# Sunboost.net
KiCad netlist of a schematic drawn in Altium Designer
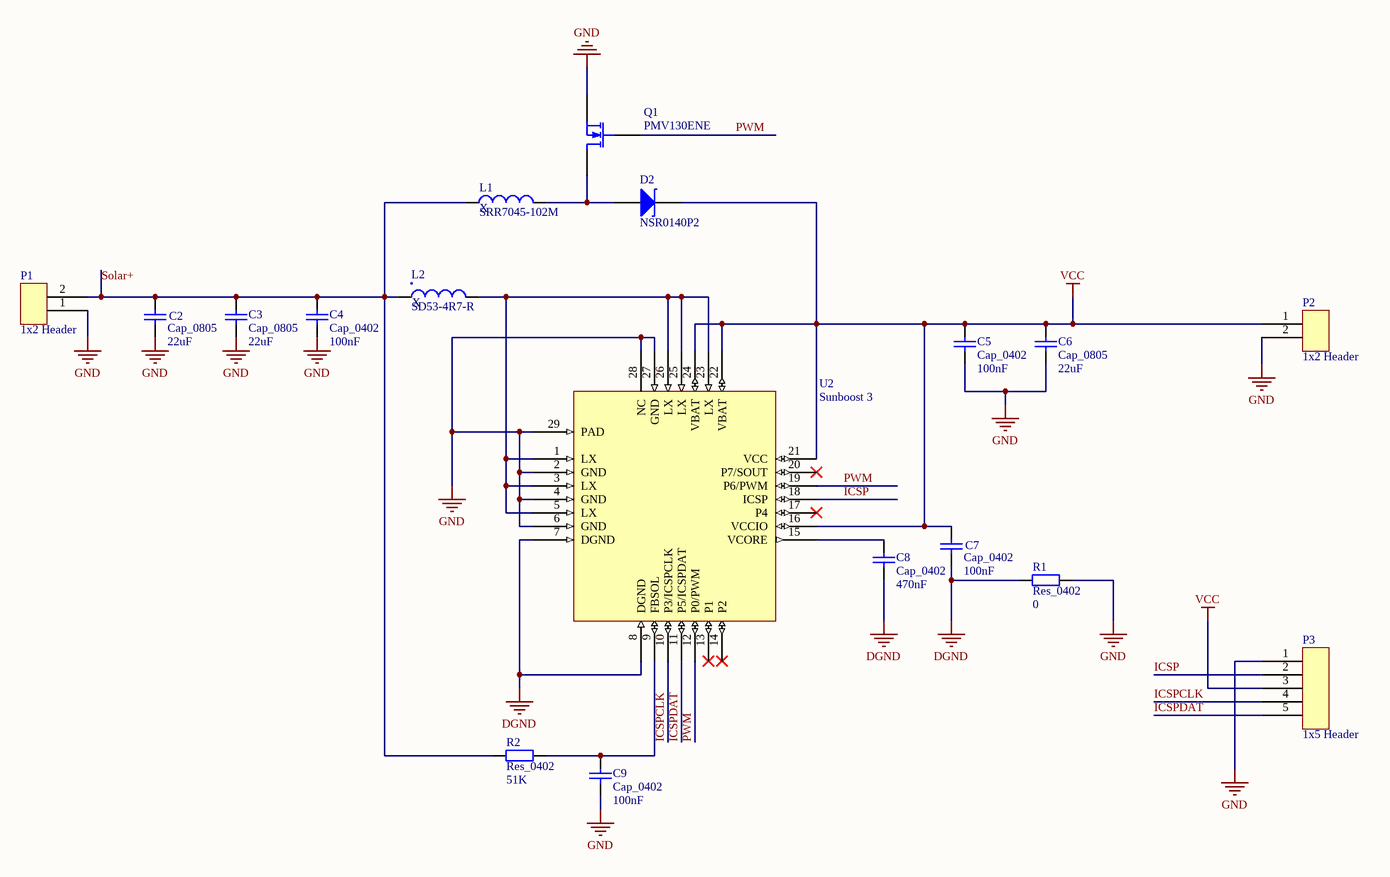
[diagram p0: Sunboost.SchDoc]

(export (version "E")
  (design (tool "Eeschema 10.0.6"))
  (components
    (comp (ref "C2")
      (value "Cap_0805")
      (footprint "0805")
      (description "Capacitor")
      (fields (field (name "ALTIUM_VALUE") "22uF") (field (name "PUBLISHER") "Altium Limited"))
      (libsource (lib "Schematic_Components") (part "Cap_0805"))
    )
    (comp (ref "C3")
      (value "Cap_0805")
      (footprint "0805")
      (description "Capacitor")
      (fields (field (name "ALTIUM_VALUE") "22uF") (field (name "PUBLISHER") "Altium Limited"))
      (libsource (lib "Schematic_Components") (part "Cap_0805"))
    )
    (comp (ref "C4")
      (value "Cap_0402")
      (footprint "0402")
      (description "Capacitor")
      (fields (field (name "ALTIUM_VALUE") "100nF") (field (name "PUBLISHER") "Altium Limited"))
      (libsource (lib "Schematic_Components") (part "Cap_0402"))
    )
    (comp (ref "C5")
      (value "Cap_0402")
      (footprint "0402")
      (description "Capacitor")
      (fields (field (name "ALTIUM_VALUE") "100nF") (field (name "PUBLISHER") "Altium Limited"))
      (libsource (lib "Schematic_Components") (part "Cap_0402"))
    )
    (comp (ref "C6")
      (value "Cap_0805")
      (footprint "0805")
      (description "Capacitor")
      (fields (field (name "ALTIUM_VALUE") "22uF") (field (name "PUBLISHER") "Altium Limited"))
      (libsource (lib "Schematic_Components") (part "Cap_0805"))
    )
    (comp (ref "C7")
      (value "Cap_0402")
      (footprint "0402")
      (description "Capacitor")
      (fields (field (name "ALTIUM_VALUE") "100nF") (field (name "PUBLISHER") "Altium Limited"))
      (libsource (lib "Schematic_Components") (part "Cap_0402"))
    )
    (comp (ref "C8")
      (value "Cap_0402")
      (footprint "0402")
      (description "Capacitor")
      (fields (field (name "ALTIUM_VALUE") "470nF") (field (name "PUBLISHER") "Altium Limited"))
      (libsource (lib "Schematic_Components") (part "Cap_0402"))
    )
    (comp (ref "C9")
      (value "Cap_0402")
      (footprint "0402")
      (description "Capacitor")
      (fields (field (name "ALTIUM_VALUE") "100nF") (field (name "PUBLISHER") "Altium Limited"))
      (libsource (lib "Schematic_Components") (part "Cap_0402"))
    )
    (comp (ref "D2")
      (value "NSR0140P2")
      (footprint "SOD-923")
      (description "Typical INFRARED GaAs LED")
      (fields (field (name "PUBLISHER") "Altium Limited"))
      (libsource (lib "Schematic_Components") (part "NSR0140P2"))
    )
    (comp (ref "L1")
      (value "SRR7045-102M")
      (footprint "SRR7045-102M")
      (description "Inductor")
      (fields (field (name "ALTIUM_VALUE") "X"))
      (libsource (lib "Schematic_Components") (part "SRR7045-102M"))
    )
    (comp (ref "L2")
      (value "SD53-4R7-R")
      (footprint "SD53-4R7-R")
      (description "Inductor")
      (fields (field (name "ALTIUM_VALUE") "X"))
      (libsource (lib "Schematic_Components") (part "SD53-4R7-R"))
    )
    (comp (ref "P1")
      (value "1x2 Header")
      (footprint "1x2 Header 1.27")
      (libsource (lib "Schematic_Components") (part "1x2 Header"))
    )
    (comp (ref "P2")
      (value "1x2 Header")
      (footprint "1x2 Header 1.27")
      (libsource (lib "") (part "1x2 Header_1"))
    )
    (comp (ref "P3")
      (value "1x5 Header")
      (footprint "1x5 Header 1.27")
      (libsource (lib "Schematic_Components") (part "1x5 Header"))
    )
    (comp (ref "Q1")
      (value "PMV130ENE")
      (footprint "SOT-23")
      (description "N-Channel MOSFET")
      (fields (field (name "PUBLISHER") "Altium Limited"))
      (libsource (lib "Schematic_Components") (part "PMV130ENE"))
    )
    (comp (ref "R1")
      (value "Res_0402")
      (footprint "0402")
      (description "Resistor")
      (fields (field (name "ALTIUM_VALUE") "0") (field (name "PUBLISHER") "Altium Limited"))
      (libsource (lib "Schematic_Components") (part "Res_0402"))
    )
    (comp (ref "R2")
      (value "Res_0402")
      (footprint "0402")
      (description "Resistor")
      (fields (field (name "ALTIUM_VALUE") "51K") (field (name "PUBLISHER") "Altium Limited"))
      (libsource (lib "Schematic_Components") (part "Res_0402"))
    )
    (comp (ref "U2")
      (value "Sunboost 3")
      (footprint "28-QFN_0.4mm")
      (description "Initvation Sunboost 3")
      (libsource (lib "Schematic_Components") (part "Sunboost 3"))
    )
  )
  (nets
    (net (code "1") (name "/ICSP") (class "Default")
      (node (ref "P3") (pin "2") (pintype "passive"))
      (node (ref "U2") (pin "18") (pinfunction "ICSP_18") (pintype "bidirectional"))
    )
    (net (code "2") (name "/ICSPCLK") (class "Default")
      (node (ref "P3") (pin "4") (pintype "passive"))
      (node (ref "U2") (pin "10") (pinfunction "P3/ICSPCLK_10") (pintype "bidirectional"))
    )
    (net (code "3") (name "/ICSPDAT") (class "Default")
      (node (ref "P3") (pin "5") (pintype "passive"))
      (node (ref "U2") (pin "11") (pinfunction "P5/ICSPDAT_11") (pintype "bidirectional"))
    )
    (net (code "4") (name "/PWM") (class "Default")
      (node (ref "Q1") (pin "1") (pinfunction "G_1") (pintype "passive"))
      (node (ref "U2") (pin "12") (pinfunction "P0/PWM_12") (pintype "bidirectional"))
      (node (ref "U2") (pin "19") (pinfunction "P6/PWM_19") (pintype "bidirectional"))
    )
    (net (code "5") (name "/Solar+") (class "Default")
      (node (ref "C2") (pin "2") (pinfunction "2_2") (pintype "passive"))
      (node (ref "C3") (pin "2") (pinfunction "2_2") (pintype "passive"))
      (node (ref "C4") (pin "2") (pinfunction "2_2") (pintype "passive"))
      (node (ref "L1") (pin "1") (pinfunction "1_1") (pintype "passive"))
      (node (ref "L2") (pin "1") (pinfunction "1_1") (pintype "passive"))
      (node (ref "P1") (pin "2") (pintype "passive"))
      (node (ref "R2") (pin "1") (pinfunction "1_1") (pintype "passive"))
    )
    (net (code "6") (name "DGND") (class "Default")
      (node (ref "C7") (pin "1") (pinfunction "1_1") (pintype "passive"))
      (node (ref "C8") (pin "1") (pinfunction "1_1") (pintype "passive"))
      (node (ref "R1") (pin "1") (pinfunction "1_1") (pintype "passive"))
      (node (ref "U2") (pin "7") (pinfunction "DGND_7") (pintype "input"))
      (node (ref "U2") (pin "8") (pinfunction "DGND_8") (pintype "input"))
    )
    (net (code "7") (name "GND") (class "Default")
      (node (ref "C2") (pin "1") (pinfunction "1_1") (pintype "passive"))
      (node (ref "C3") (pin "1") (pinfunction "1_1") (pintype "passive"))
      (node (ref "C4") (pin "1") (pinfunction "1_1") (pintype "passive"))
      (node (ref "C5") (pin "1") (pinfunction "1_1") (pintype "passive"))
      (node (ref "C6") (pin "1") (pinfunction "1_1") (pintype "passive"))
      (node (ref "C9") (pin "1") (pinfunction "1_1") (pintype "passive"))
      (node (ref "P1") (pin "1") (pintype "passive"))
      (node (ref "P2") (pin "2") (pintype "passive"))
      (node (ref "P3") (pin "1") (pintype "passive"))
      (node (ref "Q1") (pin "2") (pinfunction "S_2") (pintype "passive"))
      (node (ref "R1") (pin "2") (pinfunction "2_2") (pintype "passive"))
      (node (ref "U2") (pin "2") (pinfunction "GND_2") (pintype "input"))
      (node (ref "U2") (pin "27") (pinfunction "GND_27") (pintype "input"))
      (node (ref "U2") (pin "28") (pinfunction "NC_28") (pintype "passive"))
      (node (ref "U2") (pin "29") (pinfunction "PAD_29") (pintype "input"))
      (node (ref "U2") (pin "4") (pinfunction "GND_4") (pintype "input"))
      (node (ref "U2") (pin "6") (pinfunction "GND_6") (pintype "input"))
    )
    (net (code "8") (name "Net-(D2-A)") (class "Default")
      (node (ref "D2") (pin "2") (pinfunction "A_2") (pintype "passive"))
      (node (ref "L1") (pin "2") (pinfunction "2_2") (pintype "passive"))
      (node (ref "Q1") (pin "3") (pinfunction "D_3") (pintype "passive"))
    )
    (net (code "9") (name "Net-(L2-Pad2)") (class "Default")
      (node (ref "L2") (pin "2") (pinfunction "2_2") (pintype "passive"))
      (node (ref "U2") (pin "1") (pinfunction "LX_1") (pintype "input"))
      (node (ref "U2") (pin "23") (pinfunction "LX_23") (pintype "input"))
      (node (ref "U2") (pin "25") (pinfunction "LX_25") (pintype "input"))
      (node (ref "U2") (pin "26") (pinfunction "LX_26") (pintype "input"))
      (node (ref "U2") (pin "3") (pinfunction "LX_3") (pintype "input"))
      (node (ref "U2") (pin "5") (pinfunction "LX_5") (pintype "input"))
    )
    (net (code "10") (name "Net-(U2-FBSOL)") (class "Default")
      (node (ref "C9") (pin "2") (pinfunction "2_2") (pintype "passive"))
      (node (ref "R2") (pin "2") (pinfunction "2_2") (pintype "passive"))
      (node (ref "U2") (pin "9") (pinfunction "FBSOL_9") (pintype "bidirectional"))
    )
    (net (code "11") (name "Net-(U2-VCORE)") (class "Default")
      (node (ref "C8") (pin "2") (pinfunction "2_2") (pintype "passive"))
      (node (ref "U2") (pin "15") (pinfunction "VCORE_15") (pintype "output"))
    )
    (net (code "12") (name "VCC") (class "Default")
      (node (ref "C5") (pin "2") (pinfunction "2_2") (pintype "passive"))
      (node (ref "C6") (pin "2") (pinfunction "2_2") (pintype "passive"))
      (node (ref "C7") (pin "2") (pinfunction "2_2") (pintype "passive"))
      (node (ref "D2") (pin "1") (pinfunction "K_1") (pintype "passive"))
      (node (ref "P2") (pin "1") (pintype "passive"))
      (node (ref "P3") (pin "3") (pintype "passive"))
      (node (ref "U2") (pin "16") (pinfunction "VCCIO_16") (pintype "bidirectional"))
      (node (ref "U2") (pin "21") (pinfunction "VCC_21") (pintype "bidirectional"))
      (node (ref "U2") (pin "22") (pinfunction "VBAT_22") (pintype "bidirectional"))
      (node (ref "U2") (pin "24") (pinfunction "VBAT_24") (pintype "bidirectional"))
    )
    (net (code "13") (name "unconnected-(U2-P1-Pad13)") (class "Default")
      (node (ref "U2") (pin "13") (pinfunction "P1_13") (pintype "bidirectional+no_connect"))
    )
    (net (code "14") (name "unconnected-(U2-P2-Pad14)") (class "Default")
      (node (ref "U2") (pin "14") (pinfunction "P2_14") (pintype "bidirectional+no_connect"))
    )
    (net (code "15") (name "unconnected-(U2-P4-Pad17)") (class "Default")
      (node (ref "U2") (pin "17") (pinfunction "P4_17") (pintype "bidirectional+no_connect"))
    )
    (net (code "16") (name "unconnected-(U2-P7{slash}SOUT-Pad20)") (class "Default")
      (node (ref "U2") (pin "20") (pinfunction "P7/SOUT_20") (pintype "bidirectional+no_connect"))
    )
  )
)
